# HW1_1_a.net
KiCad netlist of a schematic drawn in EasyEDA
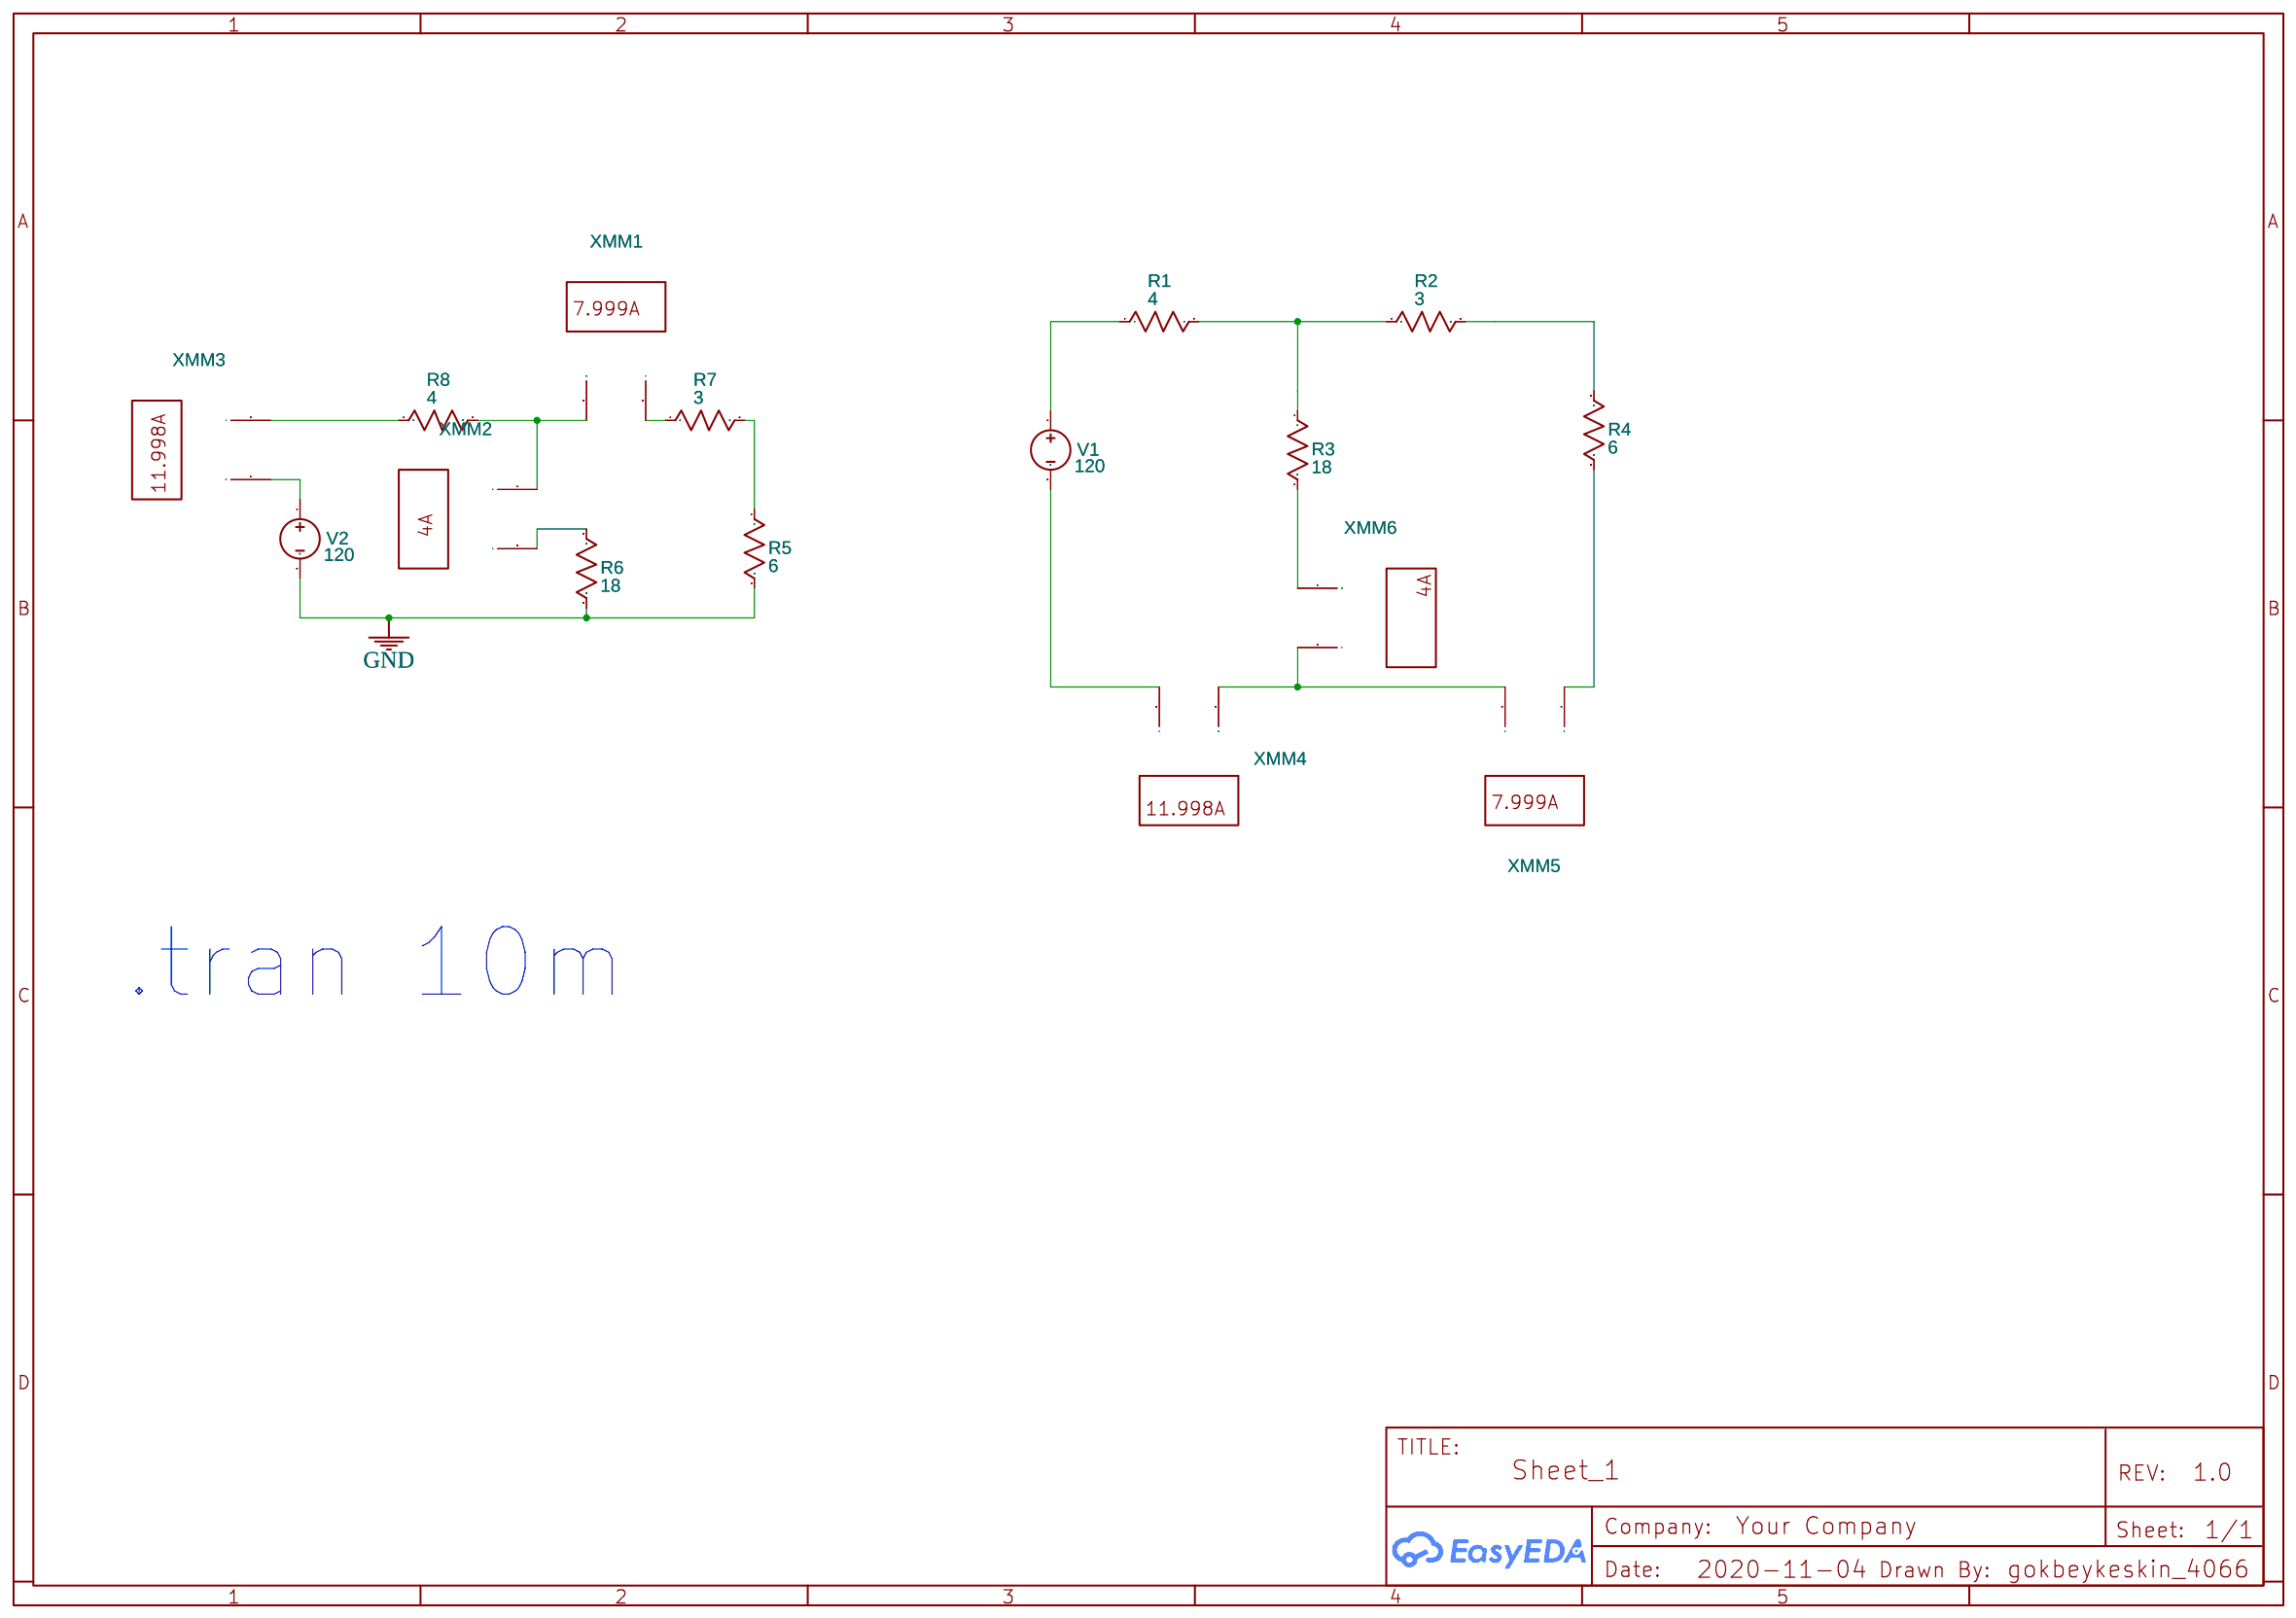
[diagram p0: schematic sheet]

(export (version "E")
  (design (tool "Eeschema 10.0.6"))
  (components
    (comp (ref "R1") (value "4") (libsource (lib "") (part "Resistor_US")))
    (comp (ref "R2") (value "3") (libsource (lib "") (part "Resistor_US")))
    (comp (ref "R3") (value "18") (libsource (lib "") (part "Resistor_US_1")))
    (comp (ref "R4") (value "6") (libsource (lib "") (part "Resistor_US_1")))
    (comp (ref "R5") (value "6") (libsource (lib "") (part "Resistor_US_1")))
    (comp (ref "R6") (value "18") (libsource (lib "") (part "Resistor_US_1")))
    (comp (ref "R7") (value "3") (libsource (lib "") (part "Resistor_US")))
    (comp (ref "R8") (value "4") (libsource (lib "") (part "Resistor_US")))
    (comp (ref "V1") (value "120") (libsource (lib "") (part "VDC")))
    (comp (ref "V2") (value "120") (libsource (lib "") (part "VDC")))
    (comp (ref "XMM1") (value "Multimeter") (libsource (lib "") (part "MULTIMETER_3")))
    (comp (ref "XMM2") (value "Multimeter") (libsource (lib "") (part "MULTIMETER_5")))
    (comp (ref "XMM3") (value "Multimeter") (libsource (lib "") (part "MULTIMETER")))
    (comp (ref "XMM4") (value "Multimeter") (libsource (lib "") (part "MULTIMETER_4")))
    (comp (ref "XMM5") (value "Multimeter") (libsource (lib "") (part "MULTIMETER_2")))
    (comp (ref "XMM6") (value "Multimeter") (libsource (lib "") (part "MULTIMETER_1")))
  )
  (nets
    (net (code "1") (name "GND") (class "Default")
      (node (ref "R5") (pin "2") (pinfunction "2_2") (pintype "unspecified"))
      (node (ref "R6") (pin "2") (pinfunction "2_2") (pintype "unspecified"))
      (node (ref "V2") (pin "2") (pinfunction "2_2") (pintype "unspecified"))
    )
    (net (code "2") (name "Net-(R1-Pad1)") (class "Default")
      (node (ref "R1") (pin "1") (pinfunction "1_1") (pintype "unspecified"))
      (node (ref "V1") (pin "1") (pinfunction "1_1") (pintype "unspecified"))
    )
    (net (code "3") (name "Net-(R1-Pad2)") (class "Default")
      (node (ref "R1") (pin "2") (pinfunction "2_2") (pintype "unspecified"))
      (node (ref "R2") (pin "1") (pinfunction "1_1") (pintype "unspecified"))
      (node (ref "R3") (pin "1") (pinfunction "1_1") (pintype "unspecified"))
    )
    (net (code "4") (name "Net-(R2-Pad2)") (class "Default")
      (node (ref "R2") (pin "2") (pinfunction "2_2") (pintype "unspecified"))
      (node (ref "R4") (pin "1") (pinfunction "1_1") (pintype "unspecified"))
    )
    (net (code "5") (name "Net-(R5-Pad1)") (class "Default")
      (node (ref "R5") (pin "1") (pinfunction "1_1") (pintype "unspecified"))
      (node (ref "R7") (pin "2") (pinfunction "2_2") (pintype "unspecified"))
    )
    (net (code "6") (name "Net-(XMM1-+)") (class "Default")
      (node (ref "R8") (pin "2") (pinfunction "2_2") (pintype "unspecified"))
      (node (ref "XMM1") (pin "1") (pinfunction "+_1") (pintype "unspecified"))
      (node (ref "XMM2") (pin "1") (pinfunction "+_1") (pintype "unspecified"))
    )
    (net (code "7") (name "Net-(XMM1-I)") (class "Default")
      (node (ref "R7") (pin "1") (pinfunction "1_1") (pintype "unspecified"))
      (node (ref "XMM1") (pin "2") (pinfunction "I_2") (pintype "unspecified"))
    )
    (net (code "8") (name "Net-(XMM2-I)") (class "Default")
      (node (ref "R6") (pin "1") (pinfunction "1_1") (pintype "unspecified"))
      (node (ref "XMM2") (pin "2") (pinfunction "I_2") (pintype "unspecified"))
    )
    (net (code "9") (name "Net-(XMM3-+)") (class "Default")
      (node (ref "V2") (pin "1") (pinfunction "1_1") (pintype "unspecified"))
      (node (ref "XMM3") (pin "1") (pinfunction "+_1") (pintype "unspecified"))
    )
    (net (code "10") (name "Net-(XMM3-I)") (class "Default")
      (node (ref "R8") (pin "1") (pinfunction "1_1") (pintype "unspecified"))
      (node (ref "XMM3") (pin "2") (pinfunction "I_2") (pintype "unspecified"))
    )
    (net (code "11") (name "Net-(XMM4-+)") (class "Default")
      (node (ref "XMM4") (pin "1") (pinfunction "+_1") (pintype "unspecified"))
      (node (ref "XMM5") (pin "2") (pinfunction "I_2") (pintype "unspecified"))
      (node (ref "XMM6") (pin "2") (pinfunction "I_2") (pintype "unspecified"))
    )
    (net (code "12") (name "Net-(XMM4-I)") (class "Default")
      (node (ref "V1") (pin "2") (pinfunction "2_2") (pintype "unspecified"))
      (node (ref "XMM4") (pin "2") (pinfunction "I_2") (pintype "unspecified"))
    )
    (net (code "13") (name "Net-(XMM5-+)") (class "Default")
      (node (ref "R4") (pin "2") (pinfunction "2_2") (pintype "unspecified"))
      (node (ref "XMM5") (pin "1") (pinfunction "+_1") (pintype "unspecified"))
    )
    (net (code "14") (name "Net-(XMM6-+)") (class "Default")
      (node (ref "R3") (pin "2") (pinfunction "2_2") (pintype "unspecified"))
      (node (ref "XMM6") (pin "1") (pinfunction "+_1") (pintype "unspecified"))
    )
  )
)
